# SCH_555-circuit_2025-11-02.net
KiCad netlist of a schematic drawn in EasyEDA
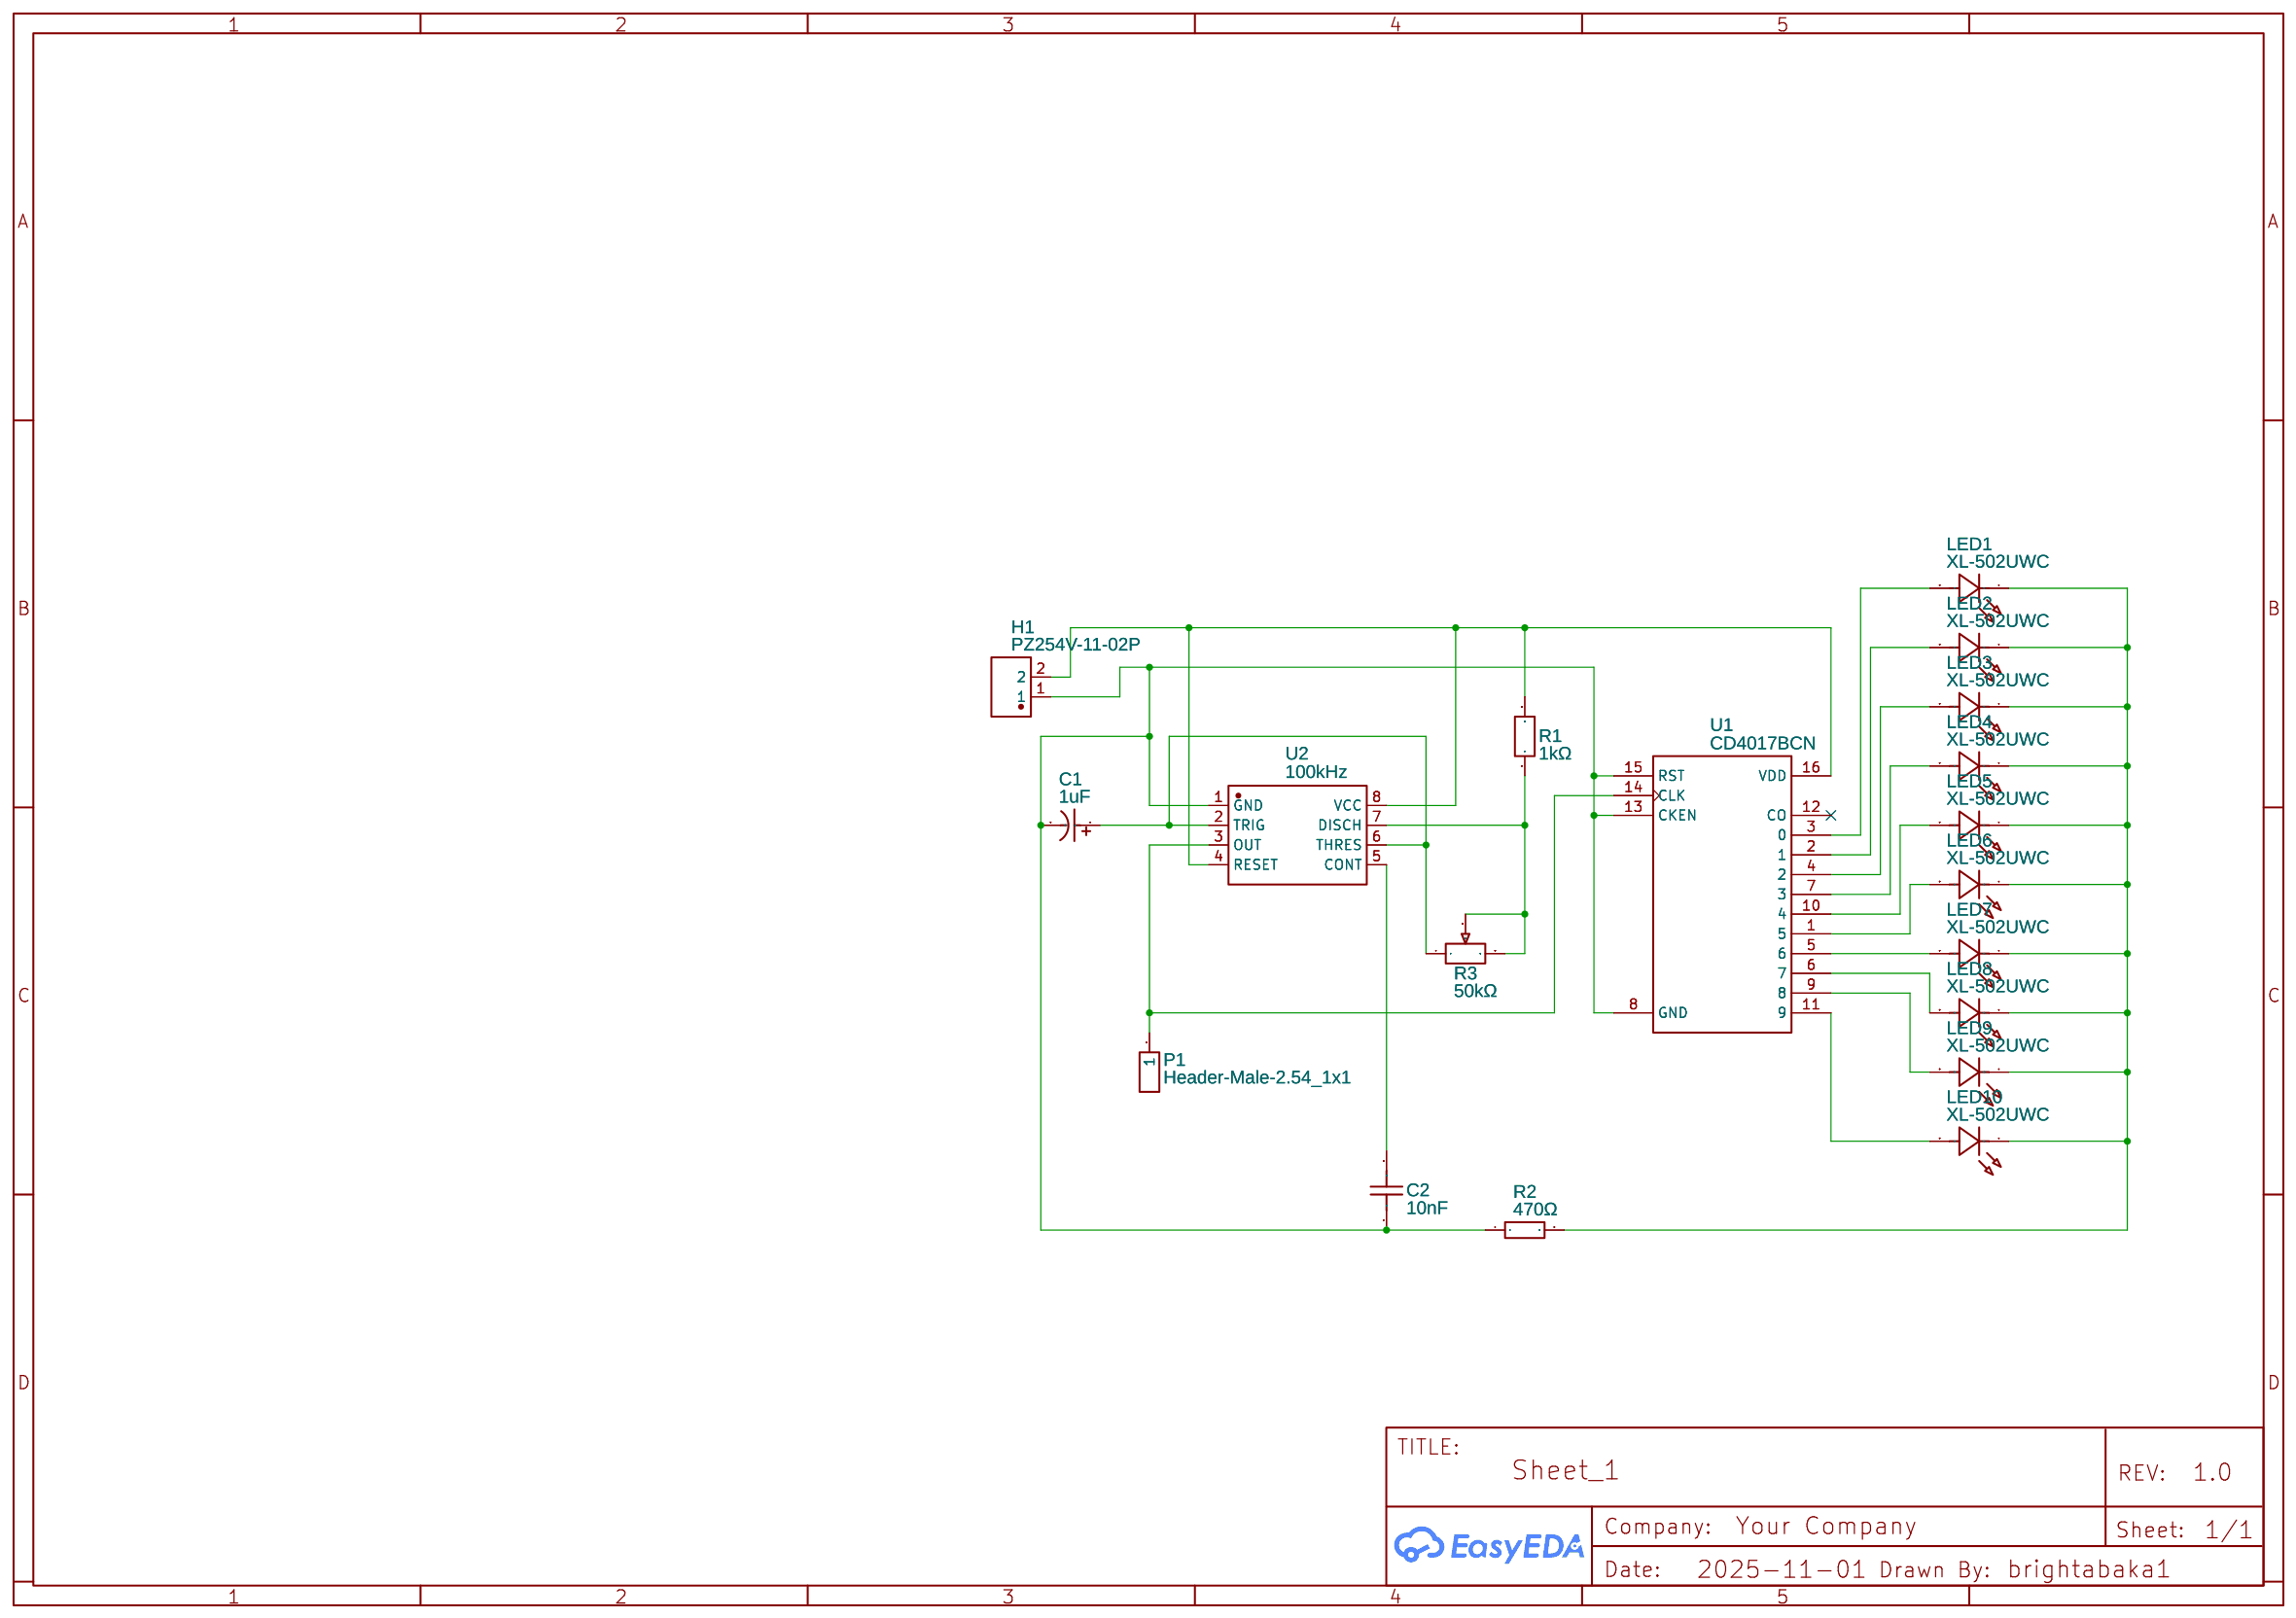
[diagram p0: schematic sheet]

(export (version "E")
  (design (tool "Eeschema 10.0.6"))
  (components
    (comp (ref "C1")
      (value "1uF")
      (fields (field (name "Manufacturer Part") "KF010M050C110A") (field (name "Manufacturer") "CapXon(丰宾)"))
      (libsource (lib "") (part "KF010M050C110A"))
    )
    (comp (ref "C2")
      (value "10nF")
      (fields (field (name "Manufacturer Part") "N09F1B103MN0B0S0N0") (field (name "Manufacturer") "STE(松田)"))
      (libsource (lib "") (part "N09F1B103MN0B0S0N0"))
    )
    (comp (ref "H1")
      (value "PZ254V-11-02P")
      (fields (field (name "Manufacturer") "XFCN(兴飞)"))
      (libsource (lib "") (part "PZ254V-11-02P"))
    )
    (comp (ref "LED1")
      (value "XL-502UWC")
      (fields (field (name "Manufacturer") "XINGLIGHT(成兴光)"))
      (libsource (lib "") (part "XL-502UWC"))
    )
    (comp (ref "LED2")
      (value "XL-502UWC")
      (fields (field (name "Manufacturer") "XINGLIGHT(成兴光)"))
      (libsource (lib "") (part "XL-502UWC"))
    )
    (comp (ref "LED3")
      (value "XL-502UWC")
      (fields (field (name "Manufacturer") "XINGLIGHT(成兴光)"))
      (libsource (lib "") (part "XL-502UWC"))
    )
    (comp (ref "LED4")
      (value "XL-502UWC")
      (fields (field (name "Manufacturer") "XINGLIGHT(成兴光)"))
      (libsource (lib "") (part "XL-502UWC"))
    )
    (comp (ref "LED5")
      (value "XL-502UWC")
      (fields (field (name "Manufacturer") "XINGLIGHT(成兴光)"))
      (libsource (lib "") (part "XL-502UWC"))
    )
    (comp (ref "LED6")
      (value "XL-502UWC")
      (fields (field (name "Manufacturer") "XINGLIGHT(成兴光)"))
      (libsource (lib "") (part "XL-502UWC"))
    )
    (comp (ref "LED7")
      (value "XL-502UWC")
      (fields (field (name "Manufacturer") "XINGLIGHT(成兴光)"))
      (libsource (lib "") (part "XL-502UWC"))
    )
    (comp (ref "LED8")
      (value "XL-502UWC")
      (fields (field (name "Manufacturer") "XINGLIGHT(成兴光)"))
      (libsource (lib "") (part "XL-502UWC"))
    )
    (comp (ref "LED9")
      (value "XL-502UWC")
      (fields (field (name "Manufacturer") "XINGLIGHT(成兴光)"))
      (libsource (lib "") (part "XL-502UWC"))
    )
    (comp (ref "LED10")
      (value "XL-502UWC")
      (fields (field (name "Manufacturer") "XINGLIGHT(成兴光)"))
      (libsource (lib "") (part "XL-502UWC"))
    )
    (comp (ref "P1")
      (value "Header-Male-2.54_1x1")
      (fields (field (name "Manufacturer Part") "2.54-1*1P针") (field (name "Manufacturer") "BOOMELE(博穆精密)"))
      (libsource (lib "") (part "Header-Male-2.54_1x1"))
    )
    (comp (ref "R1")
      (value "1kΩ")
      (fields (field (name "Manufacturer Part") "MF1/4W-1KΩ±1%T52") (field (name "Manufacturer") "华星机电"))
      (libsource (lib "") (part "MF1/4W-1KΩ±1%T52"))
    )
    (comp (ref "R2")
      (value "470Ω")
      (fields
        (field (name "Manufacturer Part") "MFR0W4F4700A50")
        (field (name "Manufacturer") "UNI-ROYAL(厚声)")
      )
      (libsource (lib "") (part "MFR0W4F4700A50"))
    )
    (comp (ref "R3")
      (value "50kΩ")
      (fields (field (name "Manufacturer Part") "3296X-1-503") (field (name "Manufacturer") "BOCHEN(博晨)"))
      (libsource (lib "") (part "3296X-1-503_C118912"))
    )
    (comp (ref "U1") (value "CD4017BCN") (libsource (lib "") (part "CD4017BCN")))
    (comp (ref "U2")
      (value "100kHz")
      (fields (field (name "Manufacturer Part") "NE555P") (field (name "Manufacturer") "TI(德州仪器)"))
      (libsource (lib "") (part "NE555P"))
    )
  )
  (nets
    (net (code "1") (name "Net-(LED1-A)") (class "Default")
      (node (ref "LED1") (pin "2") (pinfunction "A_2") (pintype "unspecified"))
      (node (ref "U1") (pin "3") (pinfunction "0_3") (pintype "output"))
    )
    (net (code "2") (name "Net-(LED1-K)") (class "Default")
      (node (ref "LED1") (pin "1") (pinfunction "K_1") (pintype "unspecified"))
      (node (ref "LED10") (pin "1") (pinfunction "K_1") (pintype "unspecified"))
      (node (ref "LED2") (pin "1") (pinfunction "K_1") (pintype "unspecified"))
      (node (ref "LED3") (pin "1") (pinfunction "K_1") (pintype "unspecified"))
      (node (ref "LED4") (pin "1") (pinfunction "K_1") (pintype "unspecified"))
      (node (ref "LED5") (pin "1") (pinfunction "K_1") (pintype "unspecified"))
      (node (ref "LED6") (pin "1") (pinfunction "K_1") (pintype "unspecified"))
      (node (ref "LED7") (pin "1") (pinfunction "K_1") (pintype "unspecified"))
      (node (ref "LED8") (pin "1") (pinfunction "K_1") (pintype "unspecified"))
      (node (ref "LED9") (pin "1") (pinfunction "K_1") (pintype "unspecified"))
      (node (ref "R2") (pin "2") (pinfunction "2_2") (pintype "input"))
    )
    (net (code "3") (name "Net-(LED2-A)") (class "Default")
      (node (ref "LED2") (pin "2") (pinfunction "A_2") (pintype "unspecified"))
      (node (ref "U1") (pin "2") (pinfunction "1_2") (pintype "output"))
    )
    (net (code "4") (name "Net-(LED3-A)") (class "Default")
      (node (ref "LED3") (pin "2") (pinfunction "A_2") (pintype "unspecified"))
      (node (ref "U1") (pin "4") (pinfunction "2_4") (pintype "output"))
    )
    (net (code "5") (name "Net-(LED4-A)") (class "Default")
      (node (ref "LED4") (pin "2") (pinfunction "A_2") (pintype "unspecified"))
      (node (ref "U1") (pin "7") (pinfunction "3_7") (pintype "output"))
    )
    (net (code "6") (name "Net-(LED5-A)") (class "Default")
      (node (ref "LED5") (pin "2") (pinfunction "A_2") (pintype "unspecified"))
      (node (ref "U1") (pin "10") (pinfunction "4_10") (pintype "output"))
    )
    (net (code "7") (name "Net-(LED6-A)") (class "Default")
      (node (ref "LED6") (pin "2") (pinfunction "A_2") (pintype "unspecified"))
      (node (ref "U1") (pin "1") (pinfunction "5_1") (pintype "output"))
    )
    (net (code "8") (name "Net-(LED7-A)") (class "Default")
      (node (ref "LED7") (pin "2") (pinfunction "A_2") (pintype "unspecified"))
      (node (ref "U1") (pin "5") (pinfunction "6_5") (pintype "output"))
    )
    (net (code "9") (name "Net-(LED8-A)") (class "Default")
      (node (ref "LED8") (pin "2") (pinfunction "A_2") (pintype "unspecified"))
      (node (ref "U1") (pin "6") (pinfunction "7_6") (pintype "output"))
    )
    (net (code "10") (name "Net-(LED9-A)") (class "Default")
      (node (ref "LED9") (pin "2") (pinfunction "A_2") (pintype "unspecified"))
      (node (ref "U1") (pin "9") (pinfunction "8_9") (pintype "output"))
    )
    (net (code "11") (name "Net-(LED10-A)") (class "Default")
      (node (ref "LED10") (pin "2") (pinfunction "A_2") (pintype "unspecified"))
      (node (ref "U1") (pin "11") (pinfunction "9_11") (pintype "output"))
    )
    (net (code "12") (name "Net-(U1-CKEN)") (class "Default")
      (node (ref "C1") (pin "2") (pinfunction "2_2") (pintype "input"))
      (node (ref "C2") (pin "1") (pinfunction "1_1") (pintype "unspecified"))
      (node (ref "H1") (pin "1") (pinfunction "1_1") (pintype "unspecified"))
      (node (ref "R2") (pin "1") (pinfunction "1_1") (pintype "input"))
      (node (ref "U1") (pin "13") (pinfunction "CKEN_13") (pintype "unspecified"))
      (node (ref "U1") (pin "15") (pinfunction "RST_15") (pintype "unspecified"))
      (node (ref "U1") (pin "8") (pinfunction "GND_8") (pintype "passive"))
      (node (ref "U2") (pin "1") (pinfunction "GND_1") (pintype "unspecified"))
    )
    (net (code "13") (name "Net-(U1-CLK)") (class "Default")
      (node (ref "P1") (pin "1") (pinfunction "1_1") (pintype "input"))
      (node (ref "U1") (pin "14") (pinfunction "CLK_14") (pintype "unspecified"))
      (node (ref "U2") (pin "3") (pinfunction "OUT_3") (pintype "unspecified"))
    )
    (net (code "14") (name "Net-(U1-VDD)") (class "Default")
      (node (ref "H1") (pin "2") (pinfunction "2_2") (pintype "unspecified"))
      (node (ref "R1") (pin "2") (pinfunction "2_2") (pintype "unspecified"))
      (node (ref "U1") (pin "16") (pinfunction "VDD_16") (pintype "passive"))
      (node (ref "U2") (pin "4") (pinfunction "RESET_4") (pintype "unspecified"))
      (node (ref "U2") (pin "8") (pinfunction "VCC_8") (pintype "unspecified"))
    )
    (net (code "15") (name "Net-(U2-CONT)") (class "Default")
      (node (ref "C2") (pin "2") (pinfunction "2_2") (pintype "unspecified"))
      (node (ref "U2") (pin "5") (pinfunction "CONT_5") (pintype "unspecified"))
    )
    (net (code "16") (name "Net-(U2-DISCH)") (class "Default")
      (node (ref "R1") (pin "1") (pinfunction "1_1") (pintype "unspecified"))
      (node (ref "R3") (pin "2") (pinfunction "2_2") (pintype "input"))
      (node (ref "R3") (pin "3") (pinfunction "3_3") (pintype "input"))
      (node (ref "U2") (pin "7") (pinfunction "DISCH_7") (pintype "unspecified"))
    )
    (net (code "17") (name "Net-(U2-THRES)") (class "Default")
      (node (ref "C1") (pin "1") (pinfunction "1_1") (pintype "input"))
      (node (ref "R3") (pin "1") (pinfunction "1_1") (pintype "input"))
      (node (ref "U2") (pin "2") (pinfunction "TRIG_2") (pintype "unspecified"))
      (node (ref "U2") (pin "6") (pinfunction "THRES_6") (pintype "unspecified"))
    )
    (net (code "18") (name "unconnected-(U1-CO-Pad12)") (class "Default")
      (node (ref "U1") (pin "12") (pinfunction "CO_12") (pintype "output+no_connect"))
    )
  )
)
